# InputConnectors.net
KiCad netlist of a schematic drawn in Altium Designer
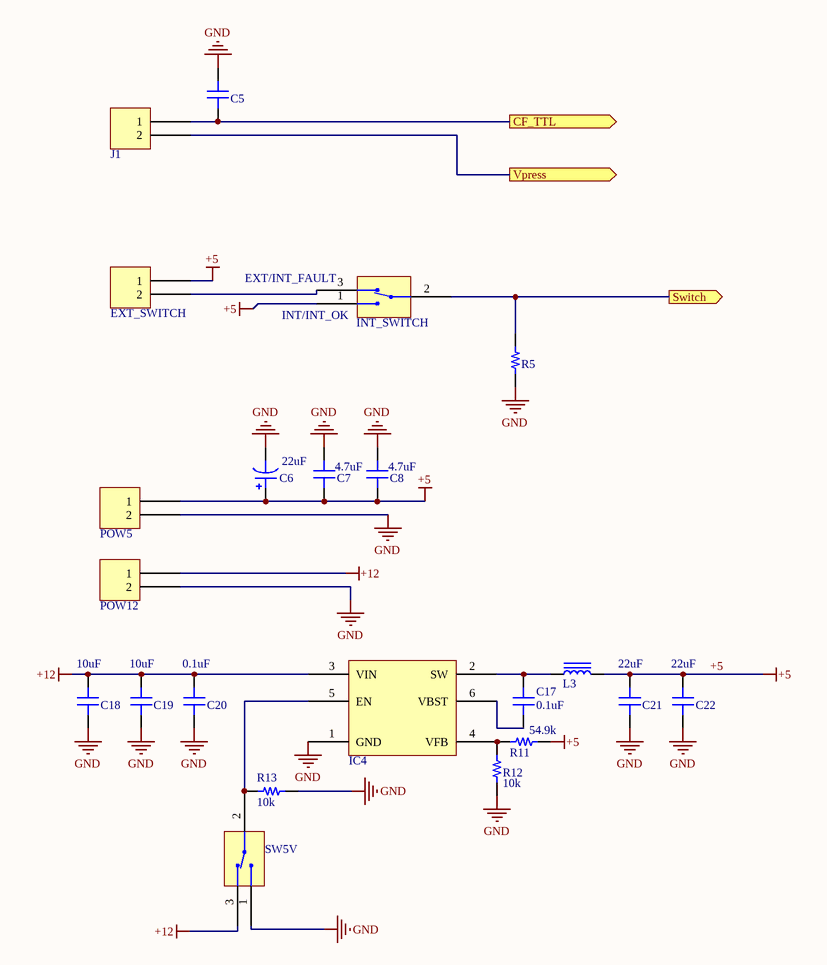
[diagram p0: InputConnectors.SchDoc]

(export (version "E")
  (design (tool "Eeschema 10.0.6"))
  (components
    (comp (ref "C5")
      (value "10000pF")
      (footprint "CAP 0805/2012")
      (description "CAP CER 10000PF 25V X7R 0805")
      (fields
        (field (name "PART NUMBER") "CL21B103KAANNNC")
        (field (name "MANUFACTURER") "Samsung Electro-Mechanics America, Inc.")
      )
      (libsource (lib "Celestial Library Database") (part "Capacitor"))
    )
    (comp (ref "C6")
      (value "22uF")
      (footprint "CAP AL TH D8 L3.5 H11.5")
      (description "CAP ALUM 22UF 20% 100V RADIAL")
      (fields
        (field (name "PART NUMBER") "EEU-FC2A220")
        (field (name "MANUFACTURER") "Panasonic Electronic Components")
      )
      (libsource (lib "Celestial Library Database") (part "Polarised Capacitor"))
    )
    (comp (ref "C7")
      (value "4.7uF")
      (footprint "CAP 1206/3216 - 1.0MM")
      (description "CAP CER 4.7UF 50V X5R 1206")
      (fields
        (field (name "PART NUMBER") "C3216X5R1H475K085AB")
        (field (name "MANUFACTURER") "TDK Corporation")
      )
      (libsource (lib "Celestial Library Database") (part "Capacitor"))
    )
    (comp (ref "C8")
      (value "4.7uF")
      (footprint "CAP 1206/3216 - 1.0MM")
      (description "CAP CER 4.7UF 50V X5R 1206")
      (fields
        (field (name "PART NUMBER") "C3216X5R1H475K085AB")
        (field (name "MANUFACTURER") "TDK Corporation")
      )
      (libsource (lib "Celestial Library Database") (part "Capacitor"))
    )
    (comp (ref "C17")
      (value "0.1uF")
      (footprint "CAP 0805/2012")
      (description "CAP CER 0.1UF 25V X7R 0805")
      (fields
        (field (name "PART NUMBER") "CL21B104KACNNNC")
        (field (name "MANUFACTURER") "Samsung Electro-Mechanics America, Inc.")
      )
      (libsource (lib "Celestial Library Database") (part "Capacitor"))
    )
    (comp (ref "C18")
      (value "10uF")
      (footprint "CAP 1206/3216")
      (description "CAP CER 10UF 25V X7R 1206")
      (fields (field (name "PART NUMBER") "C1206C106M3RACTU") (field (name "MANUFACTURER") "Kemet"))
      (libsource (lib "Celestial Library Database") (part "Capacitor"))
    )
    (comp (ref "C19")
      (value "10uF")
      (footprint "CAP 1206/3216")
      (description "CAP CER 10UF 25V X7R 1206")
      (fields (field (name "PART NUMBER") "C1206C106M3RACTU") (field (name "MANUFACTURER") "Kemet"))
      (libsource (lib "Celestial Library Database") (part "Capacitor"))
    )
    (comp (ref "C20")
      (value "0.1uF")
      (footprint "CAP 0805/2012")
      (description "CAP CER 0.1UF 25V X7R 0805")
      (fields
        (field (name "PART NUMBER") "CL21B104KACNNNC")
        (field (name "MANUFACTURER") "Samsung Electro-Mechanics America, Inc.")
      )
      (libsource (lib "Celestial Library Database") (part "Capacitor"))
    )
    (comp (ref "C21")
      (value "22uF")
      (footprint "CAP 1206/3216")
      (description "CAP CER 22UF 25V X5R 1206")
      (fields
        (field (name "PART NUMBER") "CL31A226KAHNNNE")
        (field (name "MANUFACTURER") "Samsung Electro-Mechanics America, Inc.")
      )
      (libsource (lib "Celestial Library Database") (part "Capacitor"))
    )
    (comp (ref "C22")
      (value "22uF")
      (footprint "CAP 1206/3216")
      (description "CAP CER 22UF 25V X5R 1206")
      (fields
        (field (name "PART NUMBER") "CL31A226KAHNNNE")
        (field (name "MANUFACTURER") "Samsung Electro-Mechanics America, Inc.")
      )
      (libsource (lib "Celestial Library Database") (part "Capacitor"))
    )
    (comp (ref "EXT_SWITCH")
      (value "282834-2")
      (footprint "TE 282834-2")
      (description "TERM BLOCK 2POS SIDE ENT 2.54MM")
      (fields (field (name "MANUFACTURER") "TE Connectivity AMP Connectors") (field (name "VOLTAGE") "150V"))
      (libsource (lib "Celestial Library Database") (part "2 Pin"))
    )
    (comp (ref "IC4")
      (value "TPS563201DDCT")
      (footprint "TI SOT-23-6 DDC")
      (description "IC REG BUCK ADJ 3A SYNC")
      (fields (field (name "MANUFACTURER") "Texas Instruments"))
      (libsource (lib "Celestial Library Database") (part "TI TPS563201"))
    )
    (comp (ref "INT_SWITCH")
      (value "CL-SB-12B-01T")
      (footprint "SW_CL-SB-12B-01")
      (description "SWITCH SLIDE SPDT 200MA 12V")
      (fields (field (name "MANUFACTURER") "Nidec Copal Electronics"))
      (libsource (lib "Celestial Library Database") (part "CL-SB-12B-01T"))
    )
    (comp (ref "J1")
      (value "282834-2")
      (footprint "TE 282834-2")
      (description "TERM BLOCK 2POS SIDE ENT 2.54MM")
      (fields (field (name "MANUFACTURER") "TE Connectivity AMP Connectors") (field (name "VOLTAGE") "150V"))
      (libsource (lib "Celestial Library Database") (part "2 Pin"))
    )
    (comp (ref "L3")
      (value "3.3uH")
      (footprint "WURTH WE-HCI 7050")
      (description "FIXED IND 3.3UH 9A 9 MOHM SMD")
      (fields (field (name "PART NUMBER") "744314330") (field (name "MANUFACTURER") "Wurth Electronics Inc"))
      (libsource (lib "Celestial Library Database") (part "Inductor"))
    )
    (comp (ref "POW5")
      (value "282834-2")
      (footprint "TE 282834-2")
      (description "TERM BLOCK 2POS SIDE ENT 2.54MM")
      (fields (field (name "MANUFACTURER") "TE Connectivity AMP Connectors") (field (name "VOLTAGE") "150V"))
      (libsource (lib "Celestial Library Database") (part "2 Pin"))
    )
    (comp (ref "POW12")
      (value "282834-2")
      (footprint "TE 282834-2")
      (description "TERM BLOCK 2POS SIDE ENT 2.54MM")
      (fields (field (name "MANUFACTURER") "TE Connectivity AMP Connectors") (field (name "VOLTAGE") "150V"))
      (libsource (lib "Celestial Library Database") (part "2 Pin"))
    )
    (comp (ref "R5")
      (value "10k")
      (footprint "RES 1206/3216")
      (description "RES SMD 10K OHM 1% 1/4W 1206")
      (fields
        (field (name "PART NUMBER") "ERJ-8ENF1002V")
        (field (name "MANUFACTURER") "Panasonic Electronic Components")
      )
      (libsource (lib "Celestial Library Database") (part "Resistor"))
    )
    (comp (ref "R11")
      (value "54.9k")
      (footprint "RES 0805/2012")
      (description "RES SMD 54.9K OHM 0.5% 1/2W 0805")
      (fields
        (field (name "PART NUMBER") "ERJ-P06D5492V")
        (field (name "MANUFACTURER") "Panasonic Electronic Components")
      )
      (libsource (lib "Celestial Library Database") (part "Resistor"))
    )
    (comp (ref "R12")
      (value "10k")
      (footprint "RES 0805/2012")
      (description "RES SMD 10K OHM 1% 1/2W 0805")
      (fields
        (field (name "PART NUMBER") "ERJ-P06F1002V")
        (field (name "MANUFACTURER") "Panasonic Electronic Components")
      )
      (libsource (lib "Celestial Library Database") (part "Resistor"))
    )
    (comp (ref "R13")
      (value "10k")
      (footprint "RES 0805/2012")
      (description "RES SMD 10K OHM 1% 1/2W 0805")
      (fields
        (field (name "PART NUMBER") "ERJ-P06F1002V")
        (field (name "MANUFACTURER") "Panasonic Electronic Components")
      )
      (libsource (lib "Celestial Library Database") (part "Resistor"))
    )
    (comp (ref "SW5V")
      (value "CL-SB-12B-01T")
      (footprint "SW_CL-SB-12B-01")
      (description "SWITCH SLIDE SPDT 200MA 12V")
      (fields (field (name "MANUFACTURER") "Nidec Copal Electronics"))
      (libsource (lib "") (part "CL-SB-12B-01T_1"))
    )
  )
  (nets
    (net (code "1") (name "+5") (class "Default")
      (node (ref "C21") (pin "2") (pinfunction "2_2") (pintype "passive"))
      (node (ref "C22") (pin "2") (pinfunction "2_2") (pintype "passive"))
      (node (ref "C6") (pin "1") (pinfunction "1_1") (pintype "passive"))
      (node (ref "C7") (pin "1") (pinfunction "1_1") (pintype "passive"))
      (node (ref "C8") (pin "1") (pinfunction "1_1") (pintype "passive"))
      (node (ref "EXT_SWITCH") (pin "1") (pinfunction "1_1") (pintype "passive"))
      (node (ref "INT_SWITCH") (pin "1") (pinfunction "GND_1") (pintype "passive"))
      (node (ref "L3") (pin "2") (pinfunction "2_2") (pintype "passive"))
      (node (ref "POW5") (pin "1") (pinfunction "1_1") (pintype "passive"))
      (node (ref "R11") (pin "2") (pinfunction "2_2") (pintype "passive"))
    )
    (net (code "2") (name "+12") (class "Default")
      (node (ref "C18") (pin "2") (pinfunction "2_2") (pintype "passive"))
      (node (ref "C19") (pin "2") (pinfunction "2_2") (pintype "passive"))
      (node (ref "C20") (pin "2") (pinfunction "2_2") (pintype "passive"))
      (node (ref "IC4") (pin "3") (pinfunction "VIN_3") (pintype "passive"))
      (node (ref "POW12") (pin "1") (pinfunction "1_1") (pintype "passive"))
      (node (ref "SW5V") (pin "3") (pinfunction "GND_3") (pintype "passive"))
    )
    (net (code "3") (name "/CF_TTL") (class "Default")
      (node (ref "C5") (pin "1") (pinfunction "1_1") (pintype "passive"))
      (node (ref "J1") (pin "1") (pinfunction "1_1") (pintype "passive"))
    )
    (net (code "4") (name "/Switch") (class "Default")
      (node (ref "INT_SWITCH") (pin "2") (pinfunction "GND_2") (pintype "passive"))
      (node (ref "R5") (pin "2") (pinfunction "2_2") (pintype "passive"))
    )
    (net (code "5") (name "/Vpress") (class "Default")
      (node (ref "J1") (pin "2") (pinfunction "2_2") (pintype "passive"))
    )
    (net (code "6") (name "GND") (class "Default")
      (node (ref "C18") (pin "1") (pinfunction "1_1") (pintype "passive"))
      (node (ref "C19") (pin "1") (pinfunction "1_1") (pintype "passive"))
      (node (ref "C20") (pin "1") (pinfunction "1_1") (pintype "passive"))
      (node (ref "C21") (pin "1") (pinfunction "1_1") (pintype "passive"))
      (node (ref "C22") (pin "1") (pinfunction "1_1") (pintype "passive"))
      (node (ref "C5") (pin "2") (pinfunction "2_2") (pintype "passive"))
      (node (ref "C6") (pin "2") (pinfunction "2_2") (pintype "passive"))
      (node (ref "C7") (pin "2") (pinfunction "2_2") (pintype "passive"))
      (node (ref "C8") (pin "2") (pinfunction "2_2") (pintype "passive"))
      (node (ref "IC4") (pin "1") (pinfunction "GND_1") (pintype "passive"))
      (node (ref "POW12") (pin "2") (pinfunction "2_2") (pintype "passive"))
      (node (ref "POW5") (pin "2") (pinfunction "2_2") (pintype "passive"))
      (node (ref "R12") (pin "1") (pinfunction "1_1") (pintype "passive"))
      (node (ref "R13") (pin "1") (pinfunction "1_1") (pintype "passive"))
      (node (ref "R5") (pin "1") (pinfunction "1_1") (pintype "passive"))
      (node (ref "SW5V") (pin "1") (pinfunction "GND_1") (pintype "passive"))
    )
    (net (code "7") (name "Net-(EXT_SWITCH-Pad2)") (class "Default")
      (node (ref "EXT_SWITCH") (pin "2") (pinfunction "2_2") (pintype "passive"))
      (node (ref "INT_SWITCH") (pin "3") (pinfunction "GND_3") (pintype "passive"))
    )
    (net (code "8") (name "Net-(IC4-EN)") (class "Default")
      (node (ref "IC4") (pin "5") (pinfunction "EN_5") (pintype "passive"))
      (node (ref "R13") (pin "2") (pinfunction "2_2") (pintype "passive"))
      (node (ref "SW5V") (pin "2") (pinfunction "GND_2") (pintype "passive"))
    )
    (net (code "9") (name "Net-(IC4-SW)") (class "Default")
      (node (ref "C17") (pin "2") (pinfunction "2_2") (pintype "passive"))
      (node (ref "IC4") (pin "2") (pinfunction "SW_2") (pintype "passive"))
      (node (ref "L3") (pin "1") (pinfunction "1_1") (pintype "passive"))
    )
    (net (code "10") (name "Net-(IC4-VBST)") (class "Default")
      (node (ref "C17") (pin "1") (pinfunction "1_1") (pintype "passive"))
      (node (ref "IC4") (pin "6") (pinfunction "VBST_6") (pintype "passive"))
    )
    (net (code "11") (name "Net-(IC4-VFB)") (class "Default")
      (node (ref "IC4") (pin "4") (pinfunction "VFB_4") (pintype "passive"))
      (node (ref "R11") (pin "1") (pinfunction "1_1") (pintype "passive"))
      (node (ref "R12") (pin "2") (pinfunction "2_2") (pintype "passive"))
    )
  )
)
